# Signal_Protection.net
KiCad netlist of a schematic drawn in Altium Designer
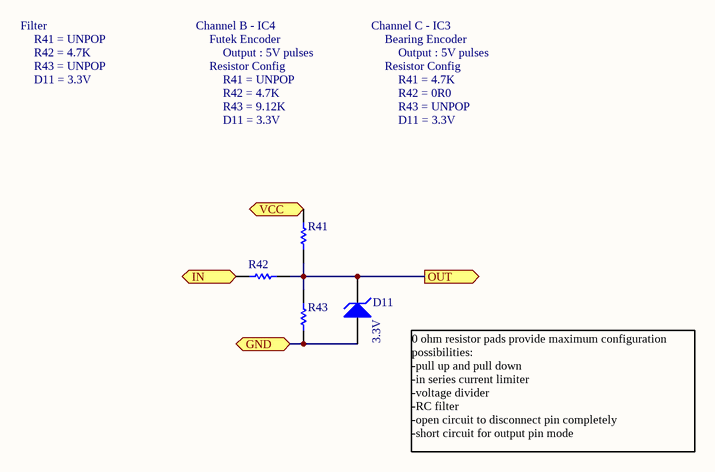
[diagram p0: Signal_Protection.SchDoc]

(export (version "E")
  (design (tool "Eeschema 10.0.6"))
  (components
    (comp (ref "D11")
      (value "DS - TVS ESD5Z3.3T1G")
      (footprint "DS-SOD523")
      (description "TVS 3.3V")
      (fields
        (field (name "MANUFACTURER") "ON Semiconductor")
        (field (name "VOLTAGE - REVERSE STANDOFF (TYP)") "3.3V")
      )
      (libsource (lib "CHINOOK_LIBRARY") (part "DS - TVS ESD5Z3.3T1G"))
    )
    (comp (ref "R41")
      (value "RS - RESISTOR")
      (footprint "RS-0603")
      (fields (field (name "TOLERANCE") "RES TOL") (field (name "POWER") "RES POWER"))
      (libsource (lib "CHINOOK_LIBRARY") (part "RS - RESISTOR"))
    )
    (comp (ref "R42")
      (value "RS - RESISTOR")
      (footprint "RS-0603")
      (fields (field (name "TOLERANCE") "RES TOL") (field (name "POWER") "RES POWER"))
      (libsource (lib "CHINOOK_LIBRARY") (part "RS - RESISTOR"))
    )
    (comp (ref "R43")
      (value "RS - RESISTOR")
      (footprint "RS-0603")
      (fields (field (name "TOLERANCE") "RES TOL") (field (name "POWER") "RES POWER"))
      (libsource (lib "CHINOOK_LIBRARY") (part "RS - RESISTOR"))
    )
  )
  (nets
    (net (code "1") (name "/GND") (class "Default")
      (node (ref "D11") (pin "A") (pinfunction "A_A") (pintype "passive"))
      (node (ref "R43") (pin "1") (pinfunction "1_1") (pintype "passive"))
    )
    (net (code "2") (name "/IN") (class "Default")
      (node (ref "R42") (pin "2") (pinfunction "2_2") (pintype "passive"))
    )
    (net (code "3") (name "/OUT") (class "Default")
      (node (ref "D11") (pin "K") (pinfunction "K_K") (pintype "passive"))
      (node (ref "R41") (pin "2") (pinfunction "2_2") (pintype "passive"))
      (node (ref "R42") (pin "1") (pinfunction "1_1") (pintype "passive"))
      (node (ref "R43") (pin "2") (pinfunction "2_2") (pintype "passive"))
    )
    (net (code "4") (name "/VCC") (class "Default")
      (node (ref "R41") (pin "1") (pinfunction "1_1") (pintype "passive"))
    )
  )
)
